# demeter_v28.net
KiCad netlist of a schematic drawn in EAGLE
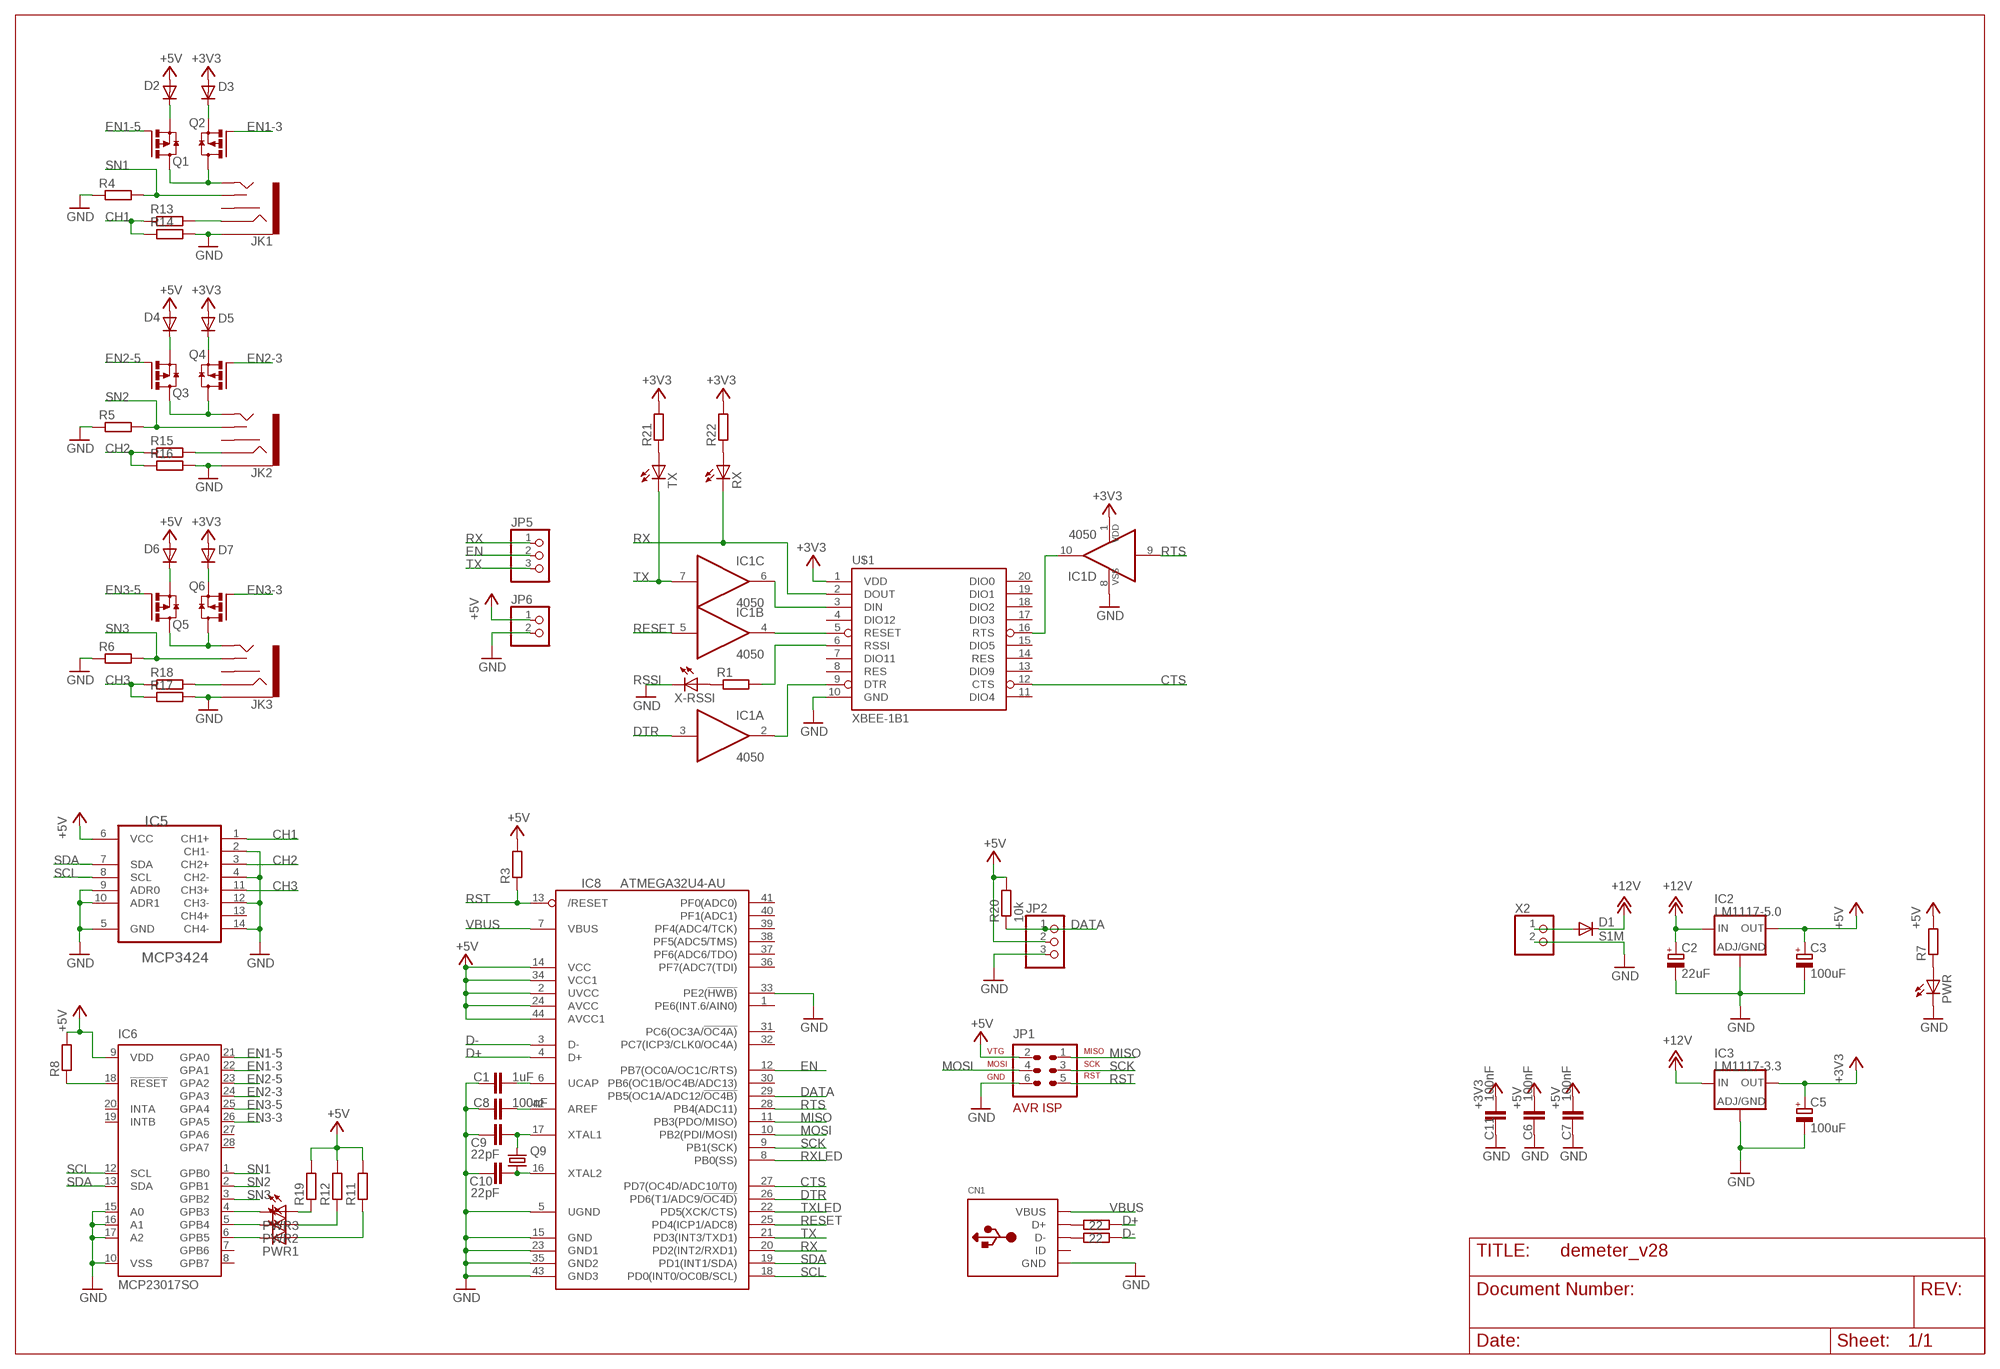
[diagram p0: schematic, sheet 1]

(export (version "E")
  (design (tool "Eeschema 10.0.6"))
  (components
    (comp (ref "C1")
      (value "1uF")
      (footprint "eagle-import:C0805K")
      (libsource (lib "eagle-import") (part "C-EUC0805K"))
    )
    (comp (ref "C2")
      (value "22uF")
      (footprint "eagle-import:PANASONIC_D")
      (libsource (lib "eagle-import") (part "CPOL-EUPD"))
    )
    (comp (ref "C3")
      (value "100uF")
      (footprint "eagle-import:PANASONIC_D")
      (libsource (lib "eagle-import") (part "CPOL-EUPD"))
    )
    (comp (ref "C5")
      (value "100uF")
      (footprint "eagle-import:PANASONIC_D")
      (libsource (lib "eagle-import") (part "CPOL-EUPD"))
    )
    (comp (ref "C6")
      (value "100nF")
      (footprint "eagle-import:C0805K")
      (libsource (lib "eagle-import") (part "C-EUC0805K"))
    )
    (comp (ref "C7")
      (value "100nF")
      (footprint "eagle-import:C0805K")
      (libsource (lib "eagle-import") (part "C-EUC0805K"))
    )
    (comp (ref "C8")
      (value "100nF")
      (footprint "eagle-import:C0805K")
      (libsource (lib "eagle-import") (part "C-EUC0805K"))
    )
    (comp (ref "C9")
      (value "22pF")
      (footprint "eagle-import:C0805K")
      (libsource (lib "eagle-import") (part "C-EUC0805K"))
    )
    (comp (ref "C10")
      (value "22pF")
      (footprint "eagle-import:C0805K")
      (libsource (lib "eagle-import") (part "C-EUC0805K"))
    )
    (comp (ref "C11")
      (value "100nF")
      (footprint "eagle-import:C0805K")
      (libsource (lib "eagle-import") (part "C-EUC0805K"))
    )
    (comp (ref "CN1")
      (value "USBMINIB")
      (footprint "eagle-import:USB-MINIB")
      (libsource (lib "eagle-import") (part "USBMINIB"))
    )
    (comp (ref "D1")
      (value "S1M")
      (footprint "eagle-import:DO-214AC")
      (libsource (lib "eagle-import") (part "S1M"))
    )
    (comp (ref "D2")
      (value "MBR0520")
      (footprint "eagle-import:SOD123")
      (libsource (lib "eagle-import") (part "MBR0520"))
    )
    (comp (ref "D3")
      (value "MBR0520")
      (footprint "eagle-import:SOD123")
      (libsource (lib "eagle-import") (part "MBR0520"))
    )
    (comp (ref "D4")
      (value "MBR0520")
      (footprint "eagle-import:SOD123")
      (libsource (lib "eagle-import") (part "MBR0520"))
    )
    (comp (ref "D5")
      (value "MBR0520")
      (footprint "eagle-import:SOD123")
      (libsource (lib "eagle-import") (part "MBR0520"))
    )
    (comp (ref "D6")
      (value "MBR0520")
      (footprint "eagle-import:SOD123")
      (libsource (lib "eagle-import") (part "MBR0520"))
    )
    (comp (ref "D7")
      (value "MBR0520")
      (footprint "eagle-import:SOD123")
      (libsource (lib "eagle-import") (part "MBR0520"))
    )
    (comp (ref "IC1")
      (value "4050")
      (footprint "eagle-import:SO16")
      (libsource (lib "eagle-import") (part "4050D"))
    )
    (comp (ref "IC2")
      (value "LM1117-5.0")
      (footprint "eagle-import:DPACK")
      (libsource (lib "eagle-import") (part "LM1117DT"))
    )
    (comp (ref "IC3")
      (value "LM1117-3.3")
      (footprint "eagle-import:DPACK")
      (libsource (lib "eagle-import") (part "LM1117DT"))
    )
    (comp (ref "IC5")
      (value "MCP3424")
      (footprint "eagle-import:SO14")
      (fields (field (name "MPN") "MCP3424-E/SL"))
      (libsource (lib "eagle-import") (part "MCP3424"))
    )
    (comp (ref "IC6")
      (value "MCP23017SO")
      (footprint "eagle-import:SO28W")
      (fields (field (name "MF") "MICROCHIP") (field (name "MPN") "MCP23017-E/SO"))
      (libsource (lib "eagle-import") (part "MCP23017SO"))
    )
    (comp (ref "IC8")
      (value "ATMEGA32U4-AU")
      (footprint "eagle-import:TQFP44")
      (libsource (lib "eagle-import") (part "ATMEGA32U4-AU"))
    )
    (comp (ref "JK1")
      (value "AUDIO-JACK2PTH")
      (footprint "eagle-import:AUDIO-JACK")
      (libsource (lib "eagle-import") (part "AUDIO-JACK2PTH"))
    )
    (comp (ref "JK2")
      (value "AUDIO-JACK2PTH")
      (footprint "eagle-import:AUDIO-JACK")
      (libsource (lib "eagle-import") (part "AUDIO-JACK2PTH"))
    )
    (comp (ref "JK3")
      (value "AUDIO-JACK2PTH")
      (footprint "eagle-import:AUDIO-JACK")
      (libsource (lib "eagle-import") (part "AUDIO-JACK2PTH"))
    )
    (comp (ref "JP1")
      (value "AVR-ISP-6")
      (footprint "eagle-import:AVR-ISP-6")
      (libsource (lib "eagle-import") (part "AVR-ISP-6"))
    )
    (comp (ref "JP2")
      (value "PINHD-1X3180")
      (footprint "eagle-import:1X03")
      (libsource (lib "eagle-import") (part "PINHD-1X3180"))
    )
    (comp (ref "JP5")
      (value "PINHD-1X3180")
      (footprint "eagle-import:1X03")
      (libsource (lib "eagle-import") (part "PINHD-1X3180"))
    )
    (comp (ref "JP6")
      (value "PINHD-1X2")
      (footprint "eagle-import:1X02")
      (libsource (lib "eagle-import") (part "PINHD-1X2"))
    )
    (comp (ref "PWR")
      (value "LED0805")
      (footprint "eagle-import:CHIP-LED0805")
      (libsource (lib "eagle-import") (part "LED0805"))
    )
    (comp (ref "PWR1")
      (value "LED0805")
      (footprint "eagle-import:CHIP-LED0805")
      (libsource (lib "eagle-import") (part "LED0805"))
    )
    (comp (ref "PWR2")
      (value "LED0805")
      (footprint "eagle-import:CHIP-LED0805")
      (libsource (lib "eagle-import") (part "LED0805"))
    )
    (comp (ref "PWR3")
      (value "LED0805")
      (footprint "eagle-import:CHIP-LED0805")
      (libsource (lib "eagle-import") (part "LED0805"))
    )
    (comp (ref "Q1")
      (value "IRLML6402")
      (footprint "eagle-import:SOT23")
      (libsource (lib "eagle-import") (part "IRLML6402"))
    )
    (comp (ref "Q2")
      (value "IRLML6402")
      (footprint "eagle-import:SOT23")
      (libsource (lib "eagle-import") (part "IRLML6402"))
    )
    (comp (ref "Q3")
      (value "IRLML6402")
      (footprint "eagle-import:SOT23")
      (libsource (lib "eagle-import") (part "IRLML6402"))
    )
    (comp (ref "Q4")
      (value "IRLML6402")
      (footprint "eagle-import:SOT23")
      (libsource (lib "eagle-import") (part "IRLML6402"))
    )
    (comp (ref "Q5")
      (value "IRLML6402")
      (footprint "eagle-import:SOT23")
      (libsource (lib "eagle-import") (part "IRLML6402"))
    )
    (comp (ref "Q6")
      (value "IRLML6402")
      (footprint "eagle-import:SOT23")
      (libsource (lib "eagle-import") (part "IRLML6402"))
    )
    (comp (ref "Q9")
      (value "CRYSTALHC49UP")
      (footprint "eagle-import:HC49UP")
      (libsource (lib "eagle-import") (part "CRYSTALHC49UP"))
    )
    (comp (ref "R1")
      (value "R-EU_R0805")
      (footprint "eagle-import:R0805")
      (libsource (lib "eagle-import") (part "R-EU_R0805"))
    )
    (comp (ref "R3")
      (value "R-EU_R0805")
      (footprint "eagle-import:R0805")
      (libsource (lib "eagle-import") (part "R-EU_R0805"))
    )
    (comp (ref "R4")
      (value "R-EU_R0805")
      (footprint "eagle-import:R0805")
      (libsource (lib "eagle-import") (part "R-EU_R0805"))
    )
    (comp (ref "R5")
      (value "R-EU_R0805")
      (footprint "eagle-import:R0805")
      (libsource (lib "eagle-import") (part "R-EU_R0805"))
    )
    (comp (ref "R6")
      (value "R-EU_R0805")
      (footprint "eagle-import:R0805")
      (libsource (lib "eagle-import") (part "R-EU_R0805"))
    )
    (comp (ref "R7")
      (value "R-EU_R0805")
      (footprint "eagle-import:R0805")
      (libsource (lib "eagle-import") (part "R-EU_R0805"))
    )
    (comp (ref "R8")
      (value "R-EU_R0805")
      (footprint "eagle-import:R0805")
      (libsource (lib "eagle-import") (part "R-EU_R0805"))
    )
    (comp (ref "R9")
      (value "22")
      (footprint "eagle-import:R0805")
      (libsource (lib "eagle-import") (part "R-EU_R0805"))
    )
    (comp (ref "R10")
      (value "22")
      (footprint "eagle-import:R0805")
      (libsource (lib "eagle-import") (part "R-EU_R0805"))
    )
    (comp (ref "R11")
      (value "R-EU_R0805")
      (footprint "eagle-import:R0805")
      (libsource (lib "eagle-import") (part "R-EU_R0805"))
    )
    (comp (ref "R12")
      (value "R-EU_R0805")
      (footprint "eagle-import:R0805")
      (libsource (lib "eagle-import") (part "R-EU_R0805"))
    )
    (comp (ref "R13")
      (value "R-EU_R0805")
      (footprint "eagle-import:R0805")
      (libsource (lib "eagle-import") (part "R-EU_R0805"))
    )
    (comp (ref "R14")
      (value "R-EU_R0805")
      (footprint "eagle-import:R0805")
      (libsource (lib "eagle-import") (part "R-EU_R0805"))
    )
    (comp (ref "R15")
      (value "R-EU_R0805")
      (footprint "eagle-import:R0805")
      (libsource (lib "eagle-import") (part "R-EU_R0805"))
    )
    (comp (ref "R16")
      (value "R-EU_R0805")
      (footprint "eagle-import:R0805")
      (libsource (lib "eagle-import") (part "R-EU_R0805"))
    )
    (comp (ref "R17")
      (value "R-EU_R0805")
      (footprint "eagle-import:R0805")
      (libsource (lib "eagle-import") (part "R-EU_R0805"))
    )
    (comp (ref "R18")
      (value "R-EU_R0805")
      (footprint "eagle-import:R0805")
      (libsource (lib "eagle-import") (part "R-EU_R0805"))
    )
    (comp (ref "R19")
      (value "R-EU_R0805")
      (footprint "eagle-import:R0805")
      (libsource (lib "eagle-import") (part "R-EU_R0805"))
    )
    (comp (ref "R20")
      (value "10k")
      (footprint "eagle-import:R0805")
      (libsource (lib "eagle-import") (part "R-EU_R0805"))
    )
    (comp (ref "R21")
      (value "R-EU_R0805")
      (footprint "eagle-import:R0805")
      (libsource (lib "eagle-import") (part "R-EU_R0805"))
    )
    (comp (ref "R22")
      (value "R-EU_R0805")
      (footprint "eagle-import:R0805")
      (libsource (lib "eagle-import") (part "R-EU_R0805"))
    )
    (comp (ref "RX")
      (value "LED0805")
      (footprint "eagle-import:CHIP-LED0805")
      (libsource (lib "eagle-import") (part "LED0805"))
    )
    (comp (ref "TX")
      (value "LED0805")
      (footprint "eagle-import:CHIP-LED0805")
      (libsource (lib "eagle-import") (part "LED0805"))
    )
    (comp (ref "U$1")
      (value "XBEE-1B1")
      (footprint "eagle-import:XBEE-1")
      (libsource (lib "eagle-import") (part "XBEE-1B1"))
    )
    (comp (ref "X-RSSI")
      (value "LED0805")
      (footprint "eagle-import:CHIP-LED0805")
      (libsource (lib "eagle-import") (part "LED0805"))
    )
    (comp (ref "X2")
      (value "W237-102")
      (footprint "eagle-import:W237-102")
      (libsource (lib "eagle-import") (part "W237-102"))
    )
  )
  (nets
    (net (code "1") (name "+3V3") (class "Default")
      (node (ref "C11") (pin "1") (pinfunction "1_1") (pintype "passive"))
      (node (ref "C5") (pin "+") (pinfunction "+_+") (pintype "passive"))
      (node (ref "D3") (pin "A") (pinfunction "A_A") (pintype "passive"))
      (node (ref "D5") (pin "A") (pinfunction "A_A") (pintype "passive"))
      (node (ref "D7") (pin "A") (pinfunction "A_A") (pintype "passive"))
      (node (ref "IC1") (pin "1") (pinfunction "VDD_1") (pintype "power_in"))
      (node (ref "IC3") (pin "4") (pinfunction "OUT_4") (pintype "passive"))
      (node (ref "R21") (pin "2") (pinfunction "2_2") (pintype "passive"))
      (node (ref "R22") (pin "2") (pinfunction "2_2") (pintype "passive"))
      (node (ref "U$1") (pin "1") (pinfunction "VDD_1") (pintype "power_in"))
    )
    (net (code "2") (name "+5V") (class "Default")
      (node (ref "C3") (pin "+") (pinfunction "+_+") (pintype "passive"))
      (node (ref "C6") (pin "1") (pinfunction "1_1") (pintype "passive"))
      (node (ref "C7") (pin "1") (pinfunction "1_1") (pintype "passive"))
      (node (ref "D2") (pin "A") (pinfunction "A_A") (pintype "passive"))
      (node (ref "D4") (pin "A") (pinfunction "A_A") (pintype "passive"))
      (node (ref "D6") (pin "A") (pinfunction "A_A") (pintype "passive"))
      (node (ref "IC2") (pin "4") (pinfunction "OUT_4") (pintype "passive"))
      (node (ref "IC5") (pin "6") (pinfunction "VCC_6") (pintype "power_in"))
      (node (ref "IC6") (pin "9") (pinfunction "VDD_9") (pintype "power_in"))
      (node (ref "IC8") (pin "14") (pinfunction "VCC_14") (pintype "bidirectional"))
      (node (ref "IC8") (pin "2") (pinfunction "UVCC_2") (pintype "bidirectional"))
      (node (ref "IC8") (pin "24") (pinfunction "AVCC_24") (pintype "bidirectional"))
      (node (ref "IC8") (pin "34") (pinfunction "VCC1_34") (pintype "bidirectional"))
      (node (ref "IC8") (pin "44") (pinfunction "AVCC1_44") (pintype "bidirectional"))
      (node (ref "JP1") (pin "2") (pinfunction "VTG_2") (pintype "passive"))
      (node (ref "JP2") (pin "2") (pinfunction "2_2") (pintype "passive"))
      (node (ref "JP6") (pin "1") (pinfunction "1_1") (pintype "passive"))
      (node (ref "R11") (pin "2") (pinfunction "2_2") (pintype "passive"))
      (node (ref "R12") (pin "2") (pinfunction "2_2") (pintype "passive"))
      (node (ref "R19") (pin "2") (pinfunction "2_2") (pintype "passive"))
      (node (ref "R20") (pin "2") (pinfunction "2_2") (pintype "passive"))
      (node (ref "R3") (pin "2") (pinfunction "2_2") (pintype "passive"))
      (node (ref "R7") (pin "2") (pinfunction "2_2") (pintype "passive"))
      (node (ref "R8") (pin "2") (pinfunction "2_2") (pintype "passive"))
    )
    (net (code "3") (name "+12V") (class "Default")
      (node (ref "C2") (pin "+") (pinfunction "+_+") (pintype "passive"))
      (node (ref "D1") (pin "C") (pinfunction "C_C") (pintype "passive"))
      (node (ref "IC2") (pin "3") (pinfunction "IN_3") (pintype "input"))
      (node (ref "IC3") (pin "3") (pinfunction "IN_3") (pintype "input"))
    )
    (net (code "4") (name "/CH1") (class "Default")
      (node (ref "IC5") (pin "1") (pinfunction "CH1+_1") (pintype "input"))
      (node (ref "R13") (pin "1") (pinfunction "1_1") (pintype "passive"))
      (node (ref "R14") (pin "1") (pinfunction "1_1") (pintype "passive"))
    )
    (net (code "5") (name "/CH2") (class "Default")
      (node (ref "IC5") (pin "3") (pinfunction "CH2+_3") (pintype "input"))
      (node (ref "R15") (pin "1") (pinfunction "1_1") (pintype "passive"))
      (node (ref "R16") (pin "1") (pinfunction "1_1") (pintype "passive"))
    )
    (net (code "6") (name "/CH3") (class "Default")
      (node (ref "IC5") (pin "11") (pinfunction "CH3+_11") (pintype "input"))
      (node (ref "R17") (pin "1") (pinfunction "1_1") (pintype "passive"))
      (node (ref "R18") (pin "1") (pinfunction "1_1") (pintype "passive"))
    )
    (net (code "7") (name "/CTS") (class "Default")
      (node (ref "IC8") (pin "27") (pinfunction "PD7(OC4D/ADC10/T0)_27") (pintype "bidirectional"))
      (node (ref "U$1") (pin "12") (pinfunction "CTS_12") (pintype "output"))
    )
    (net (code "8") (name "/D+") (class "Default")
      (node (ref "IC8") (pin "4") (pinfunction "D+_4") (pintype "bidirectional"))
      (node (ref "R9") (pin "1") (pinfunction "1_1") (pintype "passive"))
    )
    (net (code "9") (name "/D-") (class "Default")
      (node (ref "IC8") (pin "3") (pinfunction "D-_3") (pintype "bidirectional"))
      (node (ref "R10") (pin "1") (pinfunction "1_1") (pintype "passive"))
    )
    (net (code "10") (name "/DATA") (class "Default")
      (node (ref "IC8") (pin "29") (pinfunction "PB5(OC1A/ADC12/~{OC4B})_29") (pintype "bidirectional"))
      (node (ref "JP2") (pin "1") (pinfunction "1_1") (pintype "passive"))
      (node (ref "R20") (pin "1") (pinfunction "1_1") (pintype "passive"))
    )
    (net (code "11") (name "/DTR") (class "Default")
      (node (ref "IC1") (pin "3") (pinfunction "I_3") (pintype "input"))
      (node (ref "IC8") (pin "26") (pinfunction "PD6(T1/ADC9/~{OC4D})_26") (pintype "bidirectional"))
    )
    (net (code "12") (name "/EN") (class "Default")
      (node (ref "IC8") (pin "12") (pinfunction "PB7(OC0A/OC1C/RTS)_12") (pintype "bidirectional"))
      (node (ref "JP5") (pin "2") (pinfunction "2_2") (pintype "passive"))
    )
    (net (code "13") (name "/EN1-3") (class "Default")
      (node (ref "IC6") (pin "22") (pinfunction "GPA1_22") (pintype "bidirectional"))
      (node (ref "Q2") (pin "1") (pinfunction "G_1") (pintype "passive"))
    )
    (net (code "14") (name "/EN1-5") (class "Default")
      (node (ref "IC6") (pin "21") (pinfunction "GPA0_21") (pintype "bidirectional"))
      (node (ref "Q1") (pin "1") (pinfunction "G_1") (pintype "passive"))
    )
    (net (code "15") (name "/EN2-3") (class "Default")
      (node (ref "IC6") (pin "24") (pinfunction "GPA3_24") (pintype "bidirectional"))
      (node (ref "Q4") (pin "1") (pinfunction "G_1") (pintype "passive"))
    )
    (net (code "16") (name "/EN2-5") (class "Default")
      (node (ref "IC6") (pin "23") (pinfunction "GPA2_23") (pintype "bidirectional"))
      (node (ref "Q3") (pin "1") (pinfunction "G_1") (pintype "passive"))
    )
    (net (code "17") (name "/EN3-3") (class "Default")
      (node (ref "IC6") (pin "26") (pinfunction "GPA5_26") (pintype "bidirectional"))
      (node (ref "Q6") (pin "1") (pinfunction "G_1") (pintype "passive"))
    )
    (net (code "18") (name "/EN3-5") (class "Default")
      (node (ref "IC6") (pin "25") (pinfunction "GPA4_25") (pintype "bidirectional"))
      (node (ref "Q5") (pin "1") (pinfunction "G_1") (pintype "passive"))
    )
    (net (code "19") (name "/MISO") (class "Default")
      (node (ref "IC8") (pin "11") (pinfunction "PB3(PDO/MISO)_11") (pintype "bidirectional"))
      (node (ref "JP1") (pin "1") (pinfunction "MISO_1") (pintype "passive"))
    )
    (net (code "20") (name "/MOSI") (class "Default")
      (node (ref "IC8") (pin "10") (pinfunction "PB2(PDI/MOSI)_10") (pintype "bidirectional"))
      (node (ref "JP1") (pin "4") (pinfunction "MOSI_4") (pintype "passive"))
    )
    (net (code "21") (name "/RESET") (class "Default")
      (node (ref "IC1") (pin "5") (pinfunction "I_5") (pintype "input"))
      (node (ref "IC8") (pin "25") (pinfunction "PD4(ICP1/ADC8)_25") (pintype "bidirectional"))
    )
    (net (code "22") (name "/RSSI") (class "Default")
      (node (ref "R1") (pin "2") (pinfunction "2_2") (pintype "passive"))
      (node (ref "U$1") (pin "6") (pinfunction "RSSI_6") (pintype "bidirectional"))
    )
    (net (code "23") (name "/RST") (class "Default")
      (node (ref "IC8") (pin "13") (pinfunction "/RESET_13") (pintype "bidirectional"))
      (node (ref "JP1") (pin "5") (pinfunction "RST_5") (pintype "passive"))
      (node (ref "R3") (pin "1") (pinfunction "1_1") (pintype "passive"))
    )
    (net (code "24") (name "/RTS") (class "Default")
      (node (ref "IC1") (pin "9") (pinfunction "I_9") (pintype "input"))
      (node (ref "IC8") (pin "28") (pinfunction "PB4(ADC11)_28") (pintype "bidirectional"))
    )
    (net (code "25") (name "/RX") (class "Default")
      (node (ref "IC8") (pin "20") (pinfunction "PD2(INT2/RXD1)_20") (pintype "bidirectional"))
      (node (ref "JP5") (pin "1") (pinfunction "1_1") (pintype "passive"))
      (node (ref "RX") (pin "C") (pinfunction "C_C") (pintype "passive"))
      (node (ref "U$1") (pin "2") (pinfunction "DOUT_2") (pintype "output"))
    )
    (net (code "26") (name "/RXLED") (class "Default")
      (node (ref "IC8") (pin "8") (pinfunction "PB0(SS)_8") (pintype "bidirectional"))
    )
    (net (code "27") (name "/SCK") (class "Default")
      (node (ref "IC8") (pin "9") (pinfunction "PB1(SCK)_9") (pintype "bidirectional"))
      (node (ref "JP1") (pin "3") (pinfunction "SCK_3") (pintype "passive"))
    )
    (net (code "28") (name "/SCL") (class "Default")
      (node (ref "IC5") (pin "8") (pinfunction "SCL_8") (pintype "input"))
      (node (ref "IC6") (pin "12") (pinfunction "SCL_12") (pintype "input"))
      (node (ref "IC8") (pin "18") (pinfunction "PD0(INT0/OC0B/SCL)_18") (pintype "bidirectional"))
    )
    (net (code "29") (name "/SDA") (class "Default")
      (node (ref "IC5") (pin "7") (pinfunction "SDA_7") (pintype "bidirectional"))
      (node (ref "IC6") (pin "13") (pinfunction "SDA_13") (pintype "bidirectional"))
      (node (ref "IC8") (pin "19") (pinfunction "PD1(INT1/SDA)_19") (pintype "bidirectional"))
    )
    (net (code "30") (name "/SN1") (class "Default")
      (node (ref "IC6") (pin "1") (pinfunction "GPB0_1") (pintype "bidirectional"))
      (node (ref "JK1") (pin "TSH") (pinfunction "TSH_TSH") (pintype "bidirectional"))
      (node (ref "R4") (pin "2") (pinfunction "2_2") (pintype "passive"))
    )
    (net (code "31") (name "/SN2") (class "Default")
      (node (ref "IC6") (pin "2") (pinfunction "GPB1_2") (pintype "bidirectional"))
      (node (ref "JK2") (pin "TSH") (pinfunction "TSH_TSH") (pintype "bidirectional"))
      (node (ref "R5") (pin "2") (pinfunction "2_2") (pintype "passive"))
    )
    (net (code "32") (name "/SN3") (class "Default")
      (node (ref "IC6") (pin "3") (pinfunction "GPB2_3") (pintype "bidirectional"))
      (node (ref "JK3") (pin "TSH") (pinfunction "TSH_TSH") (pintype "bidirectional"))
      (node (ref "R6") (pin "2") (pinfunction "2_2") (pintype "passive"))
    )
    (net (code "33") (name "/TX") (class "Default")
      (node (ref "IC1") (pin "7") (pinfunction "I_7") (pintype "input"))
      (node (ref "IC8") (pin "21") (pinfunction "PD3(INT3/TXD1)_21") (pintype "bidirectional"))
      (node (ref "JP5") (pin "3") (pinfunction "3_3") (pintype "passive"))
      (node (ref "TX") (pin "C") (pinfunction "C_C") (pintype "passive"))
    )
    (net (code "34") (name "/TXLED") (class "Default")
      (node (ref "IC8") (pin "22") (pinfunction "PD5(XCK/CTS)_22") (pintype "bidirectional"))
    )
    (net (code "35") (name "/VBUS") (class "Default")
      (node (ref "CN1") (pin "VBUS") (pinfunction "VBUS_VBUS") (pintype "power_in"))
      (node (ref "IC8") (pin "7") (pinfunction "VBUS_7") (pintype "bidirectional"))
    )
    (net (code "36") (name "GND") (class "Default")
      (node (ref "C1") (pin "2") (pinfunction "2_2") (pintype "passive"))
      (node (ref "C10") (pin "2") (pinfunction "2_2") (pintype "passive"))
      (node (ref "C11") (pin "2") (pinfunction "2_2") (pintype "passive"))
      (node (ref "C2") (pin "-") (pinfunction "-_-") (pintype "passive"))
      (node (ref "C3") (pin "-") (pinfunction "-_-") (pintype "passive"))
      (node (ref "C5") (pin "-") (pinfunction "-_-") (pintype "passive"))
      (node (ref "C6") (pin "2") (pinfunction "2_2") (pintype "passive"))
      (node (ref "C7") (pin "2") (pinfunction "2_2") (pintype "passive"))
      (node (ref "C8") (pin "2") (pinfunction "2_2") (pintype "passive"))
      (node (ref "C9") (pin "2") (pinfunction "2_2") (pintype "passive"))
      (node (ref "CN1") (pin "GND") (pinfunction "GND_GND") (pintype "power_in"))
      (node (ref "CN1") (pin "GND1") (pinfunction "GND_GND1") (pintype "power_in"))
      (node (ref "CN1") (pin "GND2") (pinfunction "GND_GND2") (pintype "power_in"))
      (node (ref "CN1") (pin "GND3") (pinfunction "GND_GND3") (pintype "power_in"))
      (node (ref "CN1") (pin "GND4") (pinfunction "GND_GND4") (pintype "power_in"))
      (node (ref "IC1") (pin "8") (pinfunction "VSS_8") (pintype "power_in"))
      (node (ref "IC2") (pin "1") (pinfunction "ADJ_1") (pintype "input"))
      (node (ref "IC3") (pin "1") (pinfunction "ADJ_1") (pintype "input"))
      (node (ref "IC5") (pin "10") (pinfunction "ADR1_10") (pintype "input"))
      (node (ref "IC5") (pin "12") (pinfunction "CH3-_12") (pintype "input"))
      (node (ref "IC5") (pin "14") (pinfunction "CH4-_14") (pintype "input"))
      (node (ref "IC5") (pin "2") (pinfunction "CH1-_2") (pintype "input"))
      (node (ref "IC5") (pin "4") (pinfunction "CH2-_4") (pintype "input"))
      (node (ref "IC5") (pin "5") (pinfunction "GND_5") (pintype "power_in"))
      (node (ref "IC5") (pin "9") (pinfunction "ADR0_9") (pintype "input"))
      (node (ref "IC6") (pin "10") (pinfunction "VSS_10") (pintype "power_in"))
      (node (ref "IC6") (pin "15") (pinfunction "A0_15") (pintype "input"))
      (node (ref "IC6") (pin "16") (pinfunction "A1_16") (pintype "input"))
      (node (ref "IC6") (pin "17") (pinfunction "A2_17") (pintype "input"))
      (node (ref "IC8") (pin "15") (pinfunction "GND_15") (pintype "bidirectional"))
      (node (ref "IC8") (pin "23") (pinfunction "GND1_23") (pintype "bidirectional"))
      (node (ref "IC8") (pin "33") (pinfunction "PE2(~{HWB})_33") (pintype "bidirectional"))
      (node (ref "IC8") (pin "35") (pinfunction "GND2_35") (pintype "bidirectional"))
      (node (ref "IC8") (pin "43") (pinfunction "GND3_43") (pintype "bidirectional"))
      (node (ref "IC8") (pin "5") (pinfunction "UGND_5") (pintype "bidirectional"))
      (node (ref "JK1") (pin "SLEEVE") (pinfunction "SLEEVE_SLEEVE") (pintype "bidirectional"))
      (node (ref "JK2") (pin "SLEEVE") (pinfunction "SLEEVE_SLEEVE") (pintype "bidirectional"))
      (node (ref "JK3") (pin "SLEEVE") (pinfunction "SLEEVE_SLEEVE") (pintype "bidirectional"))
      (node (ref "JP1") (pin "6") (pinfunction "GND_6") (pintype "passive"))
      (node (ref "JP2") (pin "3") (pinfunction "3_3") (pintype "passive"))
      (node (ref "JP6") (pin "2") (pinfunction "2_2") (pintype "passive"))
      (node (ref "PWR") (pin "C") (pinfunction "C_C") (pintype "passive"))
      (node (ref "R14") (pin "2") (pinfunction "2_2") (pintype "passive"))
      (node (ref "R16") (pin "2") (pinfunction "2_2") (pintype "passive"))
      (node (ref "R17") (pin "2") (pinfunction "2_2") (pintype "passive"))
      (node (ref "R4") (pin "1") (pinfunction "1_1") (pintype "passive"))
      (node (ref "R5") (pin "1") (pinfunction "1_1") (pintype "passive"))
      (node (ref "R6") (pin "1") (pinfunction "1_1") (pintype "passive"))
      (node (ref "U$1") (pin "10") (pinfunction "GND_10") (pintype "power_in"))
      (node (ref "X-RSSI") (pin "C") (pinfunction "C_C") (pintype "passive"))
      (node (ref "X2") (pin "2") (pinfunction "2_2") (pintype "passive"))
    )
    (net (code "37") (name "Net-(CN1-PadD+)") (class "Default")
      (node (ref "CN1") (pin "D+") (pinfunction "D+_D+") (pintype "bidirectional"))
      (node (ref "R9") (pin "2") (pinfunction "2_2") (pintype "passive"))
    )
    (net (code "38") (name "Net-(CN1-PadD-)") (class "Default")
      (node (ref "CN1") (pin "D-") (pinfunction "D-_D-") (pintype "bidirectional"))
      (node (ref "R10") (pin "2") (pinfunction "2_2") (pintype "passive"))
    )
    (net (code "39") (name "Net-(D1-PadA)") (class "Default")
      (node (ref "D1") (pin "A") (pinfunction "A_A") (pintype "passive"))
      (node (ref "X2") (pin "1") (pinfunction "1_1") (pintype "passive"))
    )
    (net (code "40") (name "Net-(IC1A-O)") (class "Default")
      (node (ref "IC1") (pin "2") (pinfunction "O_2") (pintype "output"))
      (node (ref "U$1") (pin "9") (pinfunction "DTR_9") (pintype "bidirectional"))
    )
    (net (code "41") (name "Net-(IC1B-O)") (class "Default")
      (node (ref "IC1") (pin "4") (pinfunction "O_4") (pintype "output"))
      (node (ref "U$1") (pin "5") (pinfunction "RESET_5") (pintype "input"))
    )
    (net (code "42") (name "Net-(IC1C-O)") (class "Default")
      (node (ref "IC1") (pin "6") (pinfunction "O_6") (pintype "output"))
      (node (ref "U$1") (pin "3") (pinfunction "DIN_3") (pintype "input"))
    )
    (net (code "43") (name "Net-(IC1D-O)") (class "Default")
      (node (ref "IC1") (pin "10") (pinfunction "O_10") (pintype "output"))
      (node (ref "U$1") (pin "16") (pinfunction "RTS_16") (pintype "input"))
    )
    (net (code "44") (name "Net-(IC6-GPB3)") (class "Default")
      (node (ref "IC6") (pin "4") (pinfunction "GPB3_4") (pintype "bidirectional"))
      (node (ref "PWR3") (pin "C") (pinfunction "C_C") (pintype "passive"))
    )
    (net (code "45") (name "Net-(IC6-GPB4)") (class "Default")
      (node (ref "IC6") (pin "5") (pinfunction "GPB4_5") (pintype "bidirectional"))
      (node (ref "PWR2") (pin "C") (pinfunction "C_C") (pintype "passive"))
    )
    (net (code "46") (name "Net-(IC6-GPB5)") (class "Default")
      (node (ref "IC6") (pin "6") (pinfunction "GPB5_6") (pintype "bidirectional"))
      (node (ref "PWR1") (pin "C") (pinfunction "C_C") (pintype "passive"))
    )
    (net (code "47") (name "Net-(IC6-~{RESET})") (class "Default")
      (node (ref "IC6") (pin "18") (pinfunction "~{RESET}_18") (pintype "input"))
      (node (ref "R8") (pin "1") (pinfunction "1_1") (pintype "passive"))
    )
    (net (code "48") (name "Net-(IC8-AREF)") (class "Default")
      (node (ref "C8") (pin "1") (pinfunction "1_1") (pintype "passive"))
      (node (ref "IC8") (pin "42") (pinfunction "AREF_42") (pintype "bidirectional"))
    )
    (net (code "49") (name "Net-(IC8-UCAP)") (class "Default")
      (node (ref "C1") (pin "1") (pinfunction "1_1") (pintype "passive"))
      (node (ref "IC8") (pin "6") (pinfunction "UCAP_6") (pintype "bidirectional"))
    )
    (net (code "50") (name "Net-(IC8-XTAL1)") (class "Default")
      (node (ref "C9") (pin "1") (pinfunction "1_1") (pintype "passive"))
      (node (ref "IC8") (pin "17") (pinfunction "XTAL1_17") (pintype "bidirectional"))
      (node (ref "Q9") (pin "2") (pinfunction "2_2") (pintype "passive"))
    )
    (net (code "51") (name "Net-(IC8-XTAL2)") (class "Default")
      (node (ref "C10") (pin "1") (pinfunction "1_1") (pintype "passive"))
      (node (ref "IC8") (pin "16") (pinfunction "XTAL2_16") (pintype "bidirectional"))
      (node (ref "Q9") (pin "1") (pinfunction "1_1") (pintype "passive"))
    )
    (net (code "52") (name "Net-(JK1-PadRING)") (class "Default")
      (node (ref "JK1") (pin "RING") (pinfunction "RING_RING") (pintype "bidirectional"))
      (node (ref "R13") (pin "2") (pinfunction "2_2") (pintype "passive"))
    )
    (net (code "53") (name "Net-(JK2-PadRING)") (class "Default")
      (node (ref "JK2") (pin "RING") (pinfunction "RING_RING") (pintype "bidirectional"))
      (node (ref "R15") (pin "2") (pinfunction "2_2") (pintype "passive"))
    )
    (net (code "54") (name "Net-(JK3-PadRING)") (class "Default")
      (node (ref "JK3") (pin "RING") (pinfunction "RING_RING") (pintype "bidirectional"))
      (node (ref "R18") (pin "2") (pinfunction "2_2") (pintype "passive"))
    )
    (net (code "55") (name "Net-(PWR-PadA)") (class "Default")
      (node (ref "PWR") (pin "A") (pinfunction "A_A") (pintype "passive"))
      (node (ref "R7") (pin "1") (pinfunction "1_1") (pintype "passive"))
    )
    (net (code "56") (name "Net-(PWR1-PadA)") (class "Default")
      (node (ref "PWR1") (pin "A") (pinfunction "A_A") (pintype "passive"))
      (node (ref "R11") (pin "1") (pinfunction "1_1") (pintype "passive"))
    )
    (net (code "57") (name "Net-(PWR2-PadA)") (class "Default")
      (node (ref "PWR2") (pin "A") (pinfunction "A_A") (pintype "passive"))
      (node (ref "R12") (pin "1") (pinfunction "1_1") (pintype "passive"))
    )
    (net (code "58") (name "Net-(PWR3-PadA)") (class "Default")
      (node (ref "PWR3") (pin "A") (pinfunction "A_A") (pintype "passive"))
      (node (ref "R19") (pin "1") (pinfunction "1_1") (pintype "passive"))
    )
    (net (code "59") (name "Net-(Q1-D)") (class "Default")
      (node (ref "JK1") (pin "TIP") (pinfunction "TIP_TIP") (pintype "bidirectional"))
      (node (ref "Q1") (pin "3") (pinfunction "D_3") (pintype "passive"))
      (node (ref "Q2") (pin "3") (pinfunction "D_3") (pintype "passive"))
    )
    (net (code "60") (name "Net-(Q1-S)") (class "Default")
      (node (ref "D2") (pin "C") (pinfunction "C_C") (pintype "passive"))
      (node (ref "Q1") (pin "2") (pinfunction "S_2") (pintype "passive"))
    )
    (net (code "61") (name "Net-(Q2-S)") (class "Default")
      (node (ref "D3") (pin "C") (pinfunction "C_C") (pintype "passive"))
      (node (ref "Q2") (pin "2") (pinfunction "S_2") (pintype "passive"))
    )
    (net (code "62") (name "Net-(Q3-D)") (class "Default")
      (node (ref "JK2") (pin "TIP") (pinfunction "TIP_TIP") (pintype "bidirectional"))
      (node (ref "Q3") (pin "3") (pinfunction "D_3") (pintype "passive"))
      (node (ref "Q4") (pin "3") (pinfunction "D_3") (pintype "passive"))
    )
    (net (code "63") (name "Net-(Q3-S)") (class "Default")
      (node (ref "D4") (pin "C") (pinfunction "C_C") (pintype "passive"))
      (node (ref "Q3") (pin "2") (pinfunction "S_2") (pintype "passive"))
    )
    (net (code "64") (name "Net-(Q4-S)") (class "Default")
      (node (ref "D5") (pin "C") (pinfunction "C_C") (pintype "passive"))
      (node (ref "Q4") (pin "2") (pinfunction "S_2") (pintype "passive"))
    )
    (net (code "65") (name "Net-(Q5-D)") (class "Default")
      (node (ref "JK3") (pin "TIP") (pinfunction "TIP_TIP") (pintype "bidirectional"))
      (node (ref "Q5") (pin "3") (pinfunction "D_3") (pintype "passive"))
      (node (ref "Q6") (pin "3") (pinfunction "D_3") (pintype "passive"))
    )
    (net (code "66") (name "Net-(Q5-S)") (class "Default")
      (node (ref "D6") (pin "C") (pinfunction "C_C") (pintype "passive"))
      (node (ref "Q5") (pin "2") (pinfunction "S_2") (pintype "passive"))
    )
    (net (code "67") (name "Net-(Q6-S)") (class "Default")
      (node (ref "D7") (pin "C") (pinfunction "C_C") (pintype "passive"))
      (node (ref "Q6") (pin "2") (pinfunction "S_2") (pintype "passive"))
    )
    (net (code "68") (name "Net-(R1-Pad1)") (class "Default")
      (node (ref "R1") (pin "1") (pinfunction "1_1") (pintype "passive"))
      (node (ref "X-RSSI") (pin "A") (pinfunction "A_A") (pintype "passive"))
    )
    (net (code "69") (name "Net-(R21-Pad1)") (class "Default")
      (node (ref "R21") (pin "1") (pinfunction "1_1") (pintype "passive"))
      (node (ref "TX") (pin "A") (pinfunction "A_A") (pintype "passive"))
    )
    (net (code "70") (name "Net-(R22-Pad1)") (class "Default")
      (node (ref "R22") (pin "1") (pinfunction "1_1") (pintype "passive"))
      (node (ref "RX") (pin "A") (pinfunction "A_A") (pintype "passive"))
    )
    (net (code "71") (name "unconnected-(CN1-PadID)") (class "Default")
      (node (ref "CN1") (pin "ID") (pinfunction "ID_ID") (pintype "bidirectional"))
    )
    (net (code "72") (name "unconnected-(IC5-CH4+-Pad13)") (class "Default")
      (node (ref "IC5") (pin "13") (pinfunction "CH4+_13") (pintype "input"))
    )
    (net (code "73") (name "unconnected-(IC6-GPA6-Pad27)") (class "Default")
      (node (ref "IC6") (pin "27") (pinfunction "GPA6_27") (pintype "bidirectional"))
    )
    (net (code "74") (name "unconnected-(IC6-GPA7-Pad28)") (class "Default")
      (node (ref "IC6") (pin "28") (pinfunction "GPA7_28") (pintype "bidirectional"))
    )
    (net (code "75") (name "unconnected-(IC6-GPB6-Pad7)") (class "Default")
      (node (ref "IC6") (pin "7") (pinfunction "GPB6_7") (pintype "bidirectional"))
    )
    (net (code "76") (name "unconnected-(IC6-GPB7-Pad8)") (class "Default")
      (node (ref "IC6") (pin "8") (pinfunction "GPB7_8") (pintype "bidirectional"))
    )
    (net (code "77") (name "unconnected-(IC6-INTA-Pad20)") (class "Default")
      (node (ref "IC6") (pin "20") (pinfunction "INTA_20") (pintype "output"))
    )
    (net (code "78") (name "unconnected-(IC6-INTB-Pad19)") (class "Default")
      (node (ref "IC6") (pin "19") (pinfunction "INTB_19") (pintype "output"))
    )
    (net (code "79") (name "unconnected-(IC8-PB6(OC1B{slash}OC4B{slash}ADC13)-Pad30)") (class "Default")
      (node (ref "IC8") (pin "30") (pinfunction "PB6(OC1B/OC4B/ADC13)_30") (pintype "bidirectional"))
    )
    (net (code "80") (name "unconnected-(IC8-PC6(OC3A{slash}~{OC4A})-Pad31)") (class "Default")
      (node (ref "IC8") (pin "31") (pinfunction "PC6(OC3A/~{OC4A})_31") (pintype "bidirectional"))
    )
    (net (code "81") (name "unconnected-(IC8-PC7(ICP3{slash}CLK0{slash}OC4A)-Pad32)") (class "Default")
      (node (ref "IC8") (pin "32") (pinfunction "PC7(ICP3/CLK0/OC4A)_32") (pintype "bidirectional"))
    )
    (net (code "82") (name "unconnected-(IC8-PE6(INT.6{slash}AIN0)-Pad1)") (class "Default")
      (node (ref "IC8") (pin "1") (pinfunction "PE6(INT.6/AIN0)_1") (pintype "bidirectional"))
    )
    (net (code "83") (name "unconnected-(IC8-PF0(ADC0)-Pad41)") (class "Default")
      (node (ref "IC8") (pin "41") (pinfunction "PF0(ADC0)_41") (pintype "bidirectional"))
    )
    (net (code "84") (name "unconnected-(IC8-PF1(ADC1)-Pad40)") (class "Default")
      (node (ref "IC8") (pin "40") (pinfunction "PF1(ADC1)_40") (pintype "bidirectional"))
    )
    (net (code "85") (name "unconnected-(IC8-PF4(ADC4{slash}TCK)-Pad39)") (class "Default")
      (node (ref "IC8") (pin "39") (pinfunction "PF4(ADC4/TCK)_39") (pintype "bidirectional"))
    )
    (net (code "86") (name "unconnected-(IC8-PF5(ADC5{slash}TMS)-Pad38)") (class "Default")
      (node (ref "IC8") (pin "38") (pinfunction "PF5(ADC5/TMS)_38") (pintype "bidirectional"))
    )
    (net (code "87") (name "unconnected-(IC8-PF6(ADC6{slash}TDO)-Pad37)") (class "Default")
      (node (ref "IC8") (pin "37") (pinfunction "PF6(ADC6/TDO)_37") (pintype "bidirectional"))
    )
    (net (code "88") (name "unconnected-(IC8-PF7(ADC7(TDI)-Pad36)") (class "Default")
      (node (ref "IC8") (pin "36") (pinfunction "PF7(ADC7(TDI)_36") (pintype "bidirectional"))
    )
    (net (code "89") (name "unconnected-(JK1-PadRSH)") (class "Default")
      (node (ref "JK1") (pin "RSH") (pinfunction "RSH_RSH") (pintype "bidirectional"))
    )
    (net (code "90") (name "unconnected-(JK2-PadRSH)") (class "Default")
      (node (ref "JK2") (pin "RSH") (pinfunction "RSH_RSH") (pintype "bidirectional"))
    )
    (net (code "91") (name "unconnected-(JK3-PadRSH)") (class "Default")
      (node (ref "JK3") (pin "RSH") (pinfunction "RSH_RSH") (pintype "bidirectional"))
    )
    (net (code "92") (name "unconnected-(U$1-DIO0-Pad20)") (class "Default")
      (node (ref "U$1") (pin "20") (pinfunction "DIO0_20") (pintype "bidirectional"))
    )
    (net (code "93") (name "unconnected-(U$1-DIO1-Pad19)") (class "Default")
      (node (ref "U$1") (pin "19") (pinfunction "DIO1_19") (pintype "bidirectional"))
    )
    (net (code "94") (name "unconnected-(U$1-DIO2-Pad18)") (class "Default")
      (node (ref "U$1") (pin "18") (pinfunction "DIO2_18") (pintype "bidirectional"))
    )
    (net (code "95") (name "unconnected-(U$1-DIO3-Pad17)") (class "Default")
      (node (ref "U$1") (pin "17") (pinfunction "DIO3_17") (pintype "bidirectional"))
    )
    (net (code "96") (name "unconnected-(U$1-DIO4-Pad11)") (class "Default")
      (node (ref "U$1") (pin "11") (pinfunction "DIO4_11") (pintype "bidirectional"))
    )
    (net (code "97") (name "unconnected-(U$1-DIO5-Pad15)") (class "Default")
      (node (ref "U$1") (pin "15") (pinfunction "DIO5_15") (pintype "bidirectional"))
    )
    (net (code "98") (name "unconnected-(U$1-DIO9-Pad13)") (class "Default")
      (node (ref "U$1") (pin "13") (pinfunction "DIO9_13") (pintype "bidirectional"))
    )
    (net (code "99") (name "unconnected-(U$1-DIO11-Pad7)") (class "Default")
      (node (ref "U$1") (pin "7") (pinfunction "DIO11_7") (pintype "bidirectional"))
    )
    (net (code "100") (name "unconnected-(U$1-DIO12-Pad4)") (class "Default")
      (node (ref "U$1") (pin "4") (pinfunction "DIO12_4") (pintype "bidirectional"))
    )
    (net (code "101") (name "unconnected-(U$1-RES-Pad8)") (class "Default")
      (node (ref "U$1") (pin "8") (pinfunction "RES_8") (pintype "bidirectional"))
    )
    (net (code "102") (name "unconnected-(U$1-RES-Pad14)") (class "Default")
      (node (ref "U$1") (pin "14") (pinfunction "RES_14") (pintype "bidirectional"))
    )
  )
)
